# RH036_2.net
KiCad netlist of a schematic drawn in EAGLE
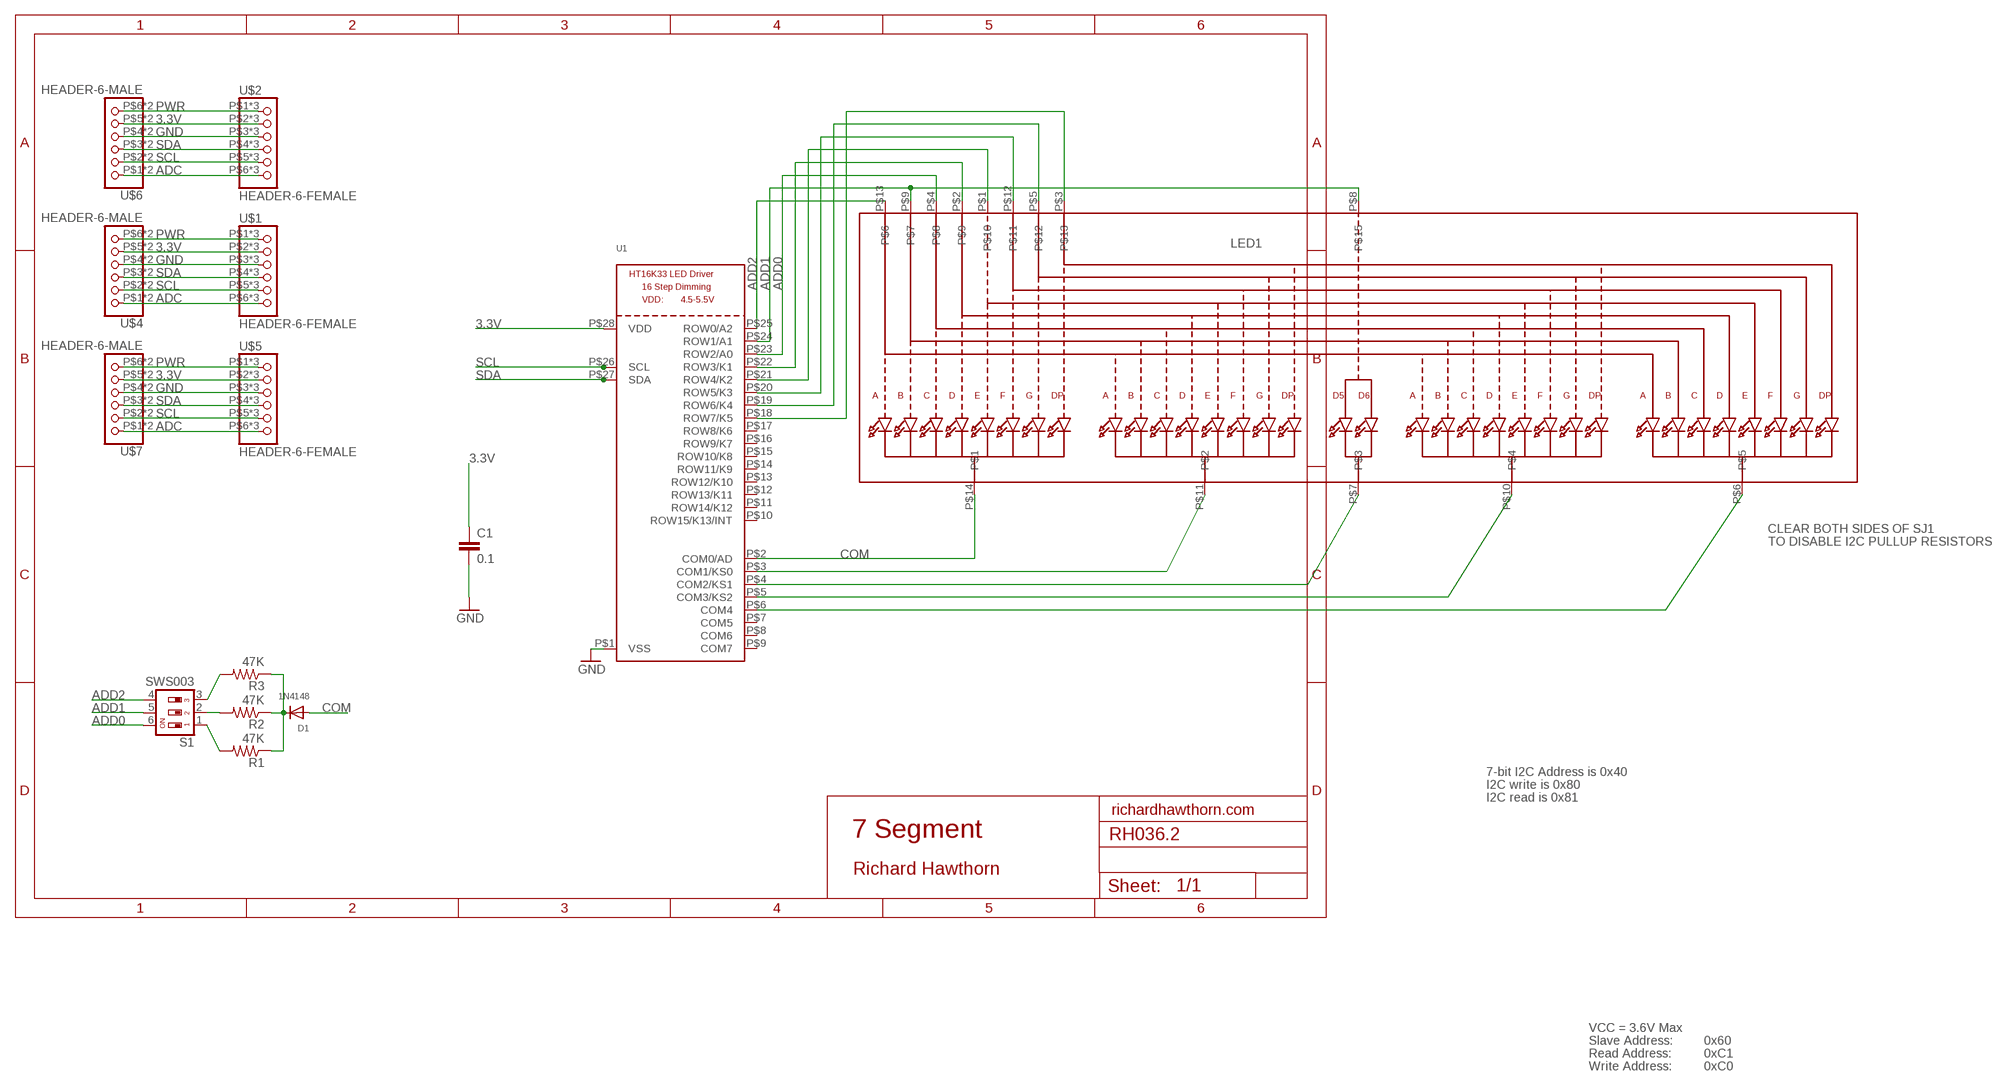
[diagram p0: schematic, sheet 1]

(export (version "E")
  (design (tool "Eeschema 10.0.6"))
  (components
    (comp (ref "C1")
      (value "0.1")
      (footprint "eagle-import:0603-CAP")
      (libsource (lib "eagle-import") (part "CAP0603-CAP"))
    )
    (comp (ref "D1")
      (value "1N4148")
      (footprint "eagle-import:SOD-323F")
      (libsource (lib "eagle-import") (part "DIODESOD-323F"))
    )
    (comp (ref "LED1")
      (value "DISP_SEGMENT_4DIGIT_BL-Q56C43")
      (footprint "eagle-import:SEGMENT-BL-Q56C43")
      (libsource (lib "eagle-import") (part "DISP_SEGMENT_4DIGIT_BL-Q56C43"))
    )
    (comp (ref "R1")
      (value "47K")
      (footprint "eagle-import:R0805")
      (libsource (lib "eagle-import") (part "R-US_R0805"))
    )
    (comp (ref "R2")
      (value "47K")
      (footprint "eagle-import:R0805")
      (libsource (lib "eagle-import") (part "R-US_R0805"))
    )
    (comp (ref "R3")
      (value "47K")
      (footprint "eagle-import:R0805")
      (libsource (lib "eagle-import") (part "R-US_R0805"))
    )
    (comp (ref "S1")
      (value "SWS003")
      (footprint "eagle-import:SMS-003")
      (libsource (lib "eagle-import") (part "SWS003"))
    )
    (comp (ref "U$1")
      (value "HEADER-6-FEMALE")
      (footprint "eagle-import:2MMHEADER6")
      (libsource (lib "eagle-import") (part "HEADER-6-FEMALE"))
    )
    (comp (ref "U$2")
      (value "HEADER-6-FEMALE")
      (footprint "eagle-import:2MMHEADER6")
      (libsource (lib "eagle-import") (part "HEADER-6-FEMALE"))
    )
    (comp (ref "U$4")
      (value "HEADER-6-MALE")
      (footprint "eagle-import:2MMHEADERPIN6")
      (libsource (lib "eagle-import") (part "HEADER-6-MALE"))
    )
    (comp (ref "U$5")
      (value "HEADER-6-FEMALE")
      (footprint "eagle-import:2MMHEADER6")
      (libsource (lib "eagle-import") (part "HEADER-6-FEMALE"))
    )
    (comp (ref "U$6")
      (value "HEADER-6-MALE")
      (footprint "eagle-import:2MMHEADERPIN6")
      (libsource (lib "eagle-import") (part "HEADER-6-MALE"))
    )
    (comp (ref "U$7")
      (value "HEADER-6-MALE")
      (footprint "eagle-import:2MMHEADERPIN6")
      (libsource (lib "eagle-import") (part "HEADER-6-MALE"))
    )
    (comp (ref "U1")
      (value "HT16K33_SOP28")
      (footprint "eagle-import:SOP28_300MIL")
      (libsource (lib "eagle-import") (part "HT16K33_SOP28"))
    )
  )
  (nets
    (net (code "1") (name "/3.3V") (class "Default")
      (node (ref "C1") (pin "1") (pinfunction "1_1") (pintype "passive"))
      (node (ref "U$1") (pin "P$10") (pinfunction "2_P$10") (pintype "passive"))
      (node (ref "U$1") (pin "P$18") (pinfunction "2_P$18") (pintype "passive"))
      (node (ref "U$1") (pin "P$2") (pinfunction "2_P$2") (pintype "passive"))
      (node (ref "U$2") (pin "P$10") (pinfunction "2_P$10") (pintype "passive"))
      (node (ref "U$2") (pin "P$18") (pinfunction "2_P$18") (pintype "passive"))
      (node (ref "U$2") (pin "P$2") (pinfunction "2_P$2") (pintype "passive"))
      (node (ref "U$4") (pin "P$13") (pinfunction "5_P$13") (pintype "passive"))
      (node (ref "U$4") (pin "P$5") (pinfunction "5_P$5") (pintype "passive"))
      (node (ref "U$5") (pin "P$10") (pinfunction "2_P$10") (pintype "passive"))
      (node (ref "U$5") (pin "P$18") (pinfunction "2_P$18") (pintype "passive"))
      (node (ref "U$5") (pin "P$2") (pinfunction "2_P$2") (pintype "passive"))
      (node (ref "U$6") (pin "P$13") (pinfunction "5_P$13") (pintype "passive"))
      (node (ref "U$6") (pin "P$5") (pinfunction "5_P$5") (pintype "passive"))
      (node (ref "U$7") (pin "P$13") (pinfunction "5_P$13") (pintype "passive"))
      (node (ref "U$7") (pin "P$5") (pinfunction "5_P$5") (pintype "passive"))
      (node (ref "U1") (pin "P$28") (pinfunction "VDD_P$28") (pintype "bidirectional"))
    )
    (net (code "2") (name "/ADC") (class "Default")
      (node (ref "U$1") (pin "P$14") (pinfunction "6_P$14") (pintype "passive"))
      (node (ref "U$1") (pin "P$22") (pinfunction "6_P$22") (pintype "passive"))
      (node (ref "U$1") (pin "P$6") (pinfunction "6_P$6") (pintype "passive"))
      (node (ref "U$2") (pin "P$14") (pinfunction "6_P$14") (pintype "passive"))
      (node (ref "U$2") (pin "P$22") (pinfunction "6_P$22") (pintype "passive"))
      (node (ref "U$2") (pin "P$6") (pinfunction "6_P$6") (pintype "passive"))
      (node (ref "U$4") (pin "P$1") (pinfunction "1_P$1") (pintype "passive"))
      (node (ref "U$4") (pin "P$9") (pinfunction "1_P$9") (pintype "passive"))
      (node (ref "U$5") (pin "P$14") (pinfunction "6_P$14") (pintype "passive"))
      (node (ref "U$5") (pin "P$22") (pinfunction "6_P$22") (pintype "passive"))
      (node (ref "U$5") (pin "P$6") (pinfunction "6_P$6") (pintype "passive"))
      (node (ref "U$6") (pin "P$1") (pinfunction "1_P$1") (pintype "passive"))
      (node (ref "U$6") (pin "P$9") (pinfunction "1_P$9") (pintype "passive"))
      (node (ref "U$7") (pin "P$1") (pinfunction "1_P$1") (pintype "passive"))
      (node (ref "U$7") (pin "P$9") (pinfunction "1_P$9") (pintype "passive"))
    )
    (net (code "3") (name "/ADD0") (class "Default")
      (node (ref "LED1") (pin "P$4") (pinfunction "P$8_P$4") (pintype "bidirectional"))
      (node (ref "S1") (pin "6") (pinfunction "6_6") (pintype "passive"))
      (node (ref "U1") (pin "P$23") (pinfunction "ROW2/A0_P$23") (pintype "bidirectional"))
    )
    (net (code "4") (name "/ADD1") (class "Default")
      (node (ref "LED1") (pin "P$8") (pinfunction "P$15_P$8") (pintype "bidirectional"))
      (node (ref "LED1") (pin "P$9") (pinfunction "P$7_P$9") (pintype "bidirectional"))
      (node (ref "S1") (pin "5") (pinfunction "5_5") (pintype "passive"))
      (node (ref "U1") (pin "P$24") (pinfunction "ROW1/A1_P$24") (pintype "bidirectional"))
    )
    (net (code "5") (name "/ADD2") (class "Default")
      (node (ref "LED1") (pin "P$13") (pinfunction "P$6_P$13") (pintype "bidirectional"))
      (node (ref "S1") (pin "4") (pinfunction "4_4") (pintype "passive"))
      (node (ref "U1") (pin "P$25") (pinfunction "ROW0/A2_P$25") (pintype "bidirectional"))
    )
    (net (code "6") (name "/COM") (class "Default")
      (node (ref "D1") (pin "A") (pinfunction "A_A") (pintype "passive"))
      (node (ref "LED1") (pin "P$14") (pinfunction "P$1_P$14") (pintype "bidirectional"))
      (node (ref "U1") (pin "P$2") (pinfunction "COM0/AD_P$2") (pintype "bidirectional"))
    )
    (net (code "7") (name "/PWR") (class "Default")
      (node (ref "U$1") (pin "P$1") (pinfunction "1_P$1") (pintype "passive"))
      (node (ref "U$1") (pin "P$17") (pinfunction "1_P$17") (pintype "passive"))
      (node (ref "U$1") (pin "P$9") (pinfunction "1_P$9") (pintype "passive"))
      (node (ref "U$2") (pin "P$1") (pinfunction "1_P$1") (pintype "passive"))
      (node (ref "U$2") (pin "P$17") (pinfunction "1_P$17") (pintype "passive"))
      (node (ref "U$2") (pin "P$9") (pinfunction "1_P$9") (pintype "passive"))
      (node (ref "U$4") (pin "P$14") (pinfunction "6_P$14") (pintype "passive"))
      (node (ref "U$4") (pin "P$6") (pinfunction "6_P$6") (pintype "passive"))
      (node (ref "U$5") (pin "P$1") (pinfunction "1_P$1") (pintype "passive"))
      (node (ref "U$5") (pin "P$17") (pinfunction "1_P$17") (pintype "passive"))
      (node (ref "U$5") (pin "P$9") (pinfunction "1_P$9") (pintype "passive"))
      (node (ref "U$6") (pin "P$14") (pinfunction "6_P$14") (pintype "passive"))
      (node (ref "U$6") (pin "P$6") (pinfunction "6_P$6") (pintype "passive"))
      (node (ref "U$7") (pin "P$14") (pinfunction "6_P$14") (pintype "passive"))
      (node (ref "U$7") (pin "P$6") (pinfunction "6_P$6") (pintype "passive"))
    )
    (net (code "8") (name "/SCL") (class "Default")
      (node (ref "U$1") (pin "P$13") (pinfunction "5_P$13") (pintype "passive"))
      (node (ref "U$1") (pin "P$21") (pinfunction "5_P$21") (pintype "passive"))
      (node (ref "U$1") (pin "P$5") (pinfunction "5_P$5") (pintype "passive"))
      (node (ref "U$2") (pin "P$13") (pinfunction "5_P$13") (pintype "passive"))
      (node (ref "U$2") (pin "P$21") (pinfunction "5_P$21") (pintype "passive"))
      (node (ref "U$2") (pin "P$5") (pinfunction "5_P$5") (pintype "passive"))
      (node (ref "U$4") (pin "P$10") (pinfunction "2_P$10") (pintype "passive"))
      (node (ref "U$4") (pin "P$2") (pinfunction "2_P$2") (pintype "passive"))
      (node (ref "U$5") (pin "P$13") (pinfunction "5_P$13") (pintype "passive"))
      (node (ref "U$5") (pin "P$21") (pinfunction "5_P$21") (pintype "passive"))
      (node (ref "U$5") (pin "P$5") (pinfunction "5_P$5") (pintype "passive"))
      (node (ref "U$6") (pin "P$10") (pinfunction "2_P$10") (pintype "passive"))
      (node (ref "U$6") (pin "P$2") (pinfunction "2_P$2") (pintype "passive"))
      (node (ref "U$7") (pin "P$10") (pinfunction "2_P$10") (pintype "passive"))
      (node (ref "U$7") (pin "P$2") (pinfunction "2_P$2") (pintype "passive"))
      (node (ref "U1") (pin "P$26") (pinfunction "SCL_P$26") (pintype "bidirectional"))
    )
    (net (code "9") (name "/SDA") (class "Default")
      (node (ref "U$1") (pin "P$12") (pinfunction "4_P$12") (pintype "passive"))
      (node (ref "U$1") (pin "P$20") (pinfunction "4_P$20") (pintype "passive"))
      (node (ref "U$1") (pin "P$4") (pinfunction "4_P$4") (pintype "passive"))
      (node (ref "U$2") (pin "P$12") (pinfunction "4_P$12") (pintype "passive"))
      (node (ref "U$2") (pin "P$20") (pinfunction "4_P$20") (pintype "passive"))
      (node (ref "U$2") (pin "P$4") (pinfunction "4_P$4") (pintype "passive"))
      (node (ref "U$4") (pin "P$11") (pinfunction "3_P$11") (pintype "passive"))
      (node (ref "U$4") (pin "P$3") (pinfunction "3_P$3") (pintype "passive"))
      (node (ref "U$5") (pin "P$12") (pinfunction "4_P$12") (pintype "passive"))
      (node (ref "U$5") (pin "P$20") (pinfunction "4_P$20") (pintype "passive"))
      (node (ref "U$5") (pin "P$4") (pinfunction "4_P$4") (pintype "passive"))
      (node (ref "U$6") (pin "P$11") (pinfunction "3_P$11") (pintype "passive"))
      (node (ref "U$6") (pin "P$3") (pinfunction "3_P$3") (pintype "passive"))
      (node (ref "U$7") (pin "P$11") (pinfunction "3_P$11") (pintype "passive"))
      (node (ref "U$7") (pin "P$3") (pinfunction "3_P$3") (pintype "passive"))
      (node (ref "U1") (pin "P$27") (pinfunction "SDA_P$27") (pintype "bidirectional"))
    )
    (net (code "10") (name "GND") (class "Default")
      (node (ref "C1") (pin "2") (pinfunction "2_2") (pintype "passive"))
      (node (ref "U$1") (pin "P$11") (pinfunction "3_P$11") (pintype "passive"))
      (node (ref "U$1") (pin "P$19") (pinfunction "3_P$19") (pintype "passive"))
      (node (ref "U$1") (pin "P$3") (pinfunction "3_P$3") (pintype "passive"))
      (node (ref "U$2") (pin "P$11") (pinfunction "3_P$11") (pintype "passive"))
      (node (ref "U$2") (pin "P$19") (pinfunction "3_P$19") (pintype "passive"))
      (node (ref "U$2") (pin "P$3") (pinfunction "3_P$3") (pintype "passive"))
      (node (ref "U$4") (pin "P$12") (pinfunction "4_P$12") (pintype "passive"))
      (node (ref "U$4") (pin "P$4") (pinfunction "4_P$4") (pintype "passive"))
      (node (ref "U$5") (pin "P$11") (pinfunction "3_P$11") (pintype "passive"))
      (node (ref "U$5") (pin "P$19") (pinfunction "3_P$19") (pintype "passive"))
      (node (ref "U$5") (pin "P$3") (pinfunction "3_P$3") (pintype "passive"))
      (node (ref "U$6") (pin "P$12") (pinfunction "4_P$12") (pintype "passive"))
      (node (ref "U$6") (pin "P$4") (pinfunction "4_P$4") (pintype "passive"))
      (node (ref "U$7") (pin "P$12") (pinfunction "4_P$12") (pintype "passive"))
      (node (ref "U$7") (pin "P$4") (pinfunction "4_P$4") (pintype "passive"))
      (node (ref "U1") (pin "P$1") (pinfunction "VSS_P$1") (pintype "bidirectional"))
    )
    (net (code "11") (name "Net-(D1-PadC)") (class "Default")
      (node (ref "D1") (pin "C") (pinfunction "C_C") (pintype "passive"))
      (node (ref "R1") (pin "1") (pinfunction "1_1") (pintype "passive"))
      (node (ref "R2") (pin "1") (pinfunction "1_1") (pintype "passive"))
      (node (ref "R3") (pin "1") (pinfunction "1_1") (pintype "passive"))
    )
    (net (code "12") (name "Net-(LED1-P$2)") (class "Default")
      (node (ref "LED1") (pin "P$11") (pinfunction "P$2_P$11") (pintype "bidirectional"))
      (node (ref "U1") (pin "P$3") (pinfunction "COM1/KS0_P$3") (pintype "bidirectional"))
    )
    (net (code "13") (name "Net-(LED1-P$3)") (class "Default")
      (node (ref "LED1") (pin "P$7") (pinfunction "P$3_P$7") (pintype "bidirectional"))
      (node (ref "U1") (pin "P$4") (pinfunction "COM2/KS1_P$4") (pintype "bidirectional"))
    )
    (net (code "14") (name "Net-(LED1-P$4)") (class "Default")
      (node (ref "LED1") (pin "P$10") (pinfunction "P$4_P$10") (pintype "bidirectional"))
      (node (ref "U1") (pin "P$5") (pinfunction "COM3/KS2_P$5") (pintype "bidirectional"))
    )
    (net (code "15") (name "Net-(LED1-P$5)") (class "Default")
      (node (ref "LED1") (pin "P$6") (pinfunction "P$5_P$6") (pintype "bidirectional"))
      (node (ref "U1") (pin "P$6") (pinfunction "COM4_P$6") (pintype "bidirectional"))
    )
    (net (code "16") (name "Net-(LED1-P$9)") (class "Default")
      (node (ref "LED1") (pin "P$2") (pinfunction "P$9_P$2") (pintype "bidirectional"))
      (node (ref "U1") (pin "P$22") (pinfunction "ROW3/K1_P$22") (pintype "bidirectional"))
    )
    (net (code "17") (name "Net-(LED1-P$10)") (class "Default")
      (node (ref "LED1") (pin "P$1") (pinfunction "P$10_P$1") (pintype "bidirectional"))
      (node (ref "U1") (pin "P$21") (pinfunction "ROW4/K2_P$21") (pintype "bidirectional"))
    )
    (net (code "18") (name "Net-(LED1-P$11)") (class "Default")
      (node (ref "LED1") (pin "P$12") (pinfunction "P$11_P$12") (pintype "bidirectional"))
      (node (ref "U1") (pin "P$20") (pinfunction "ROW5/K3_P$20") (pintype "bidirectional"))
    )
    (net (code "19") (name "Net-(LED1-P$12)") (class "Default")
      (node (ref "LED1") (pin "P$5") (pinfunction "P$12_P$5") (pintype "bidirectional"))
      (node (ref "U1") (pin "P$19") (pinfunction "ROW6/K4_P$19") (pintype "bidirectional"))
    )
    (net (code "20") (name "Net-(LED1-P$13)") (class "Default")
      (node (ref "LED1") (pin "P$3") (pinfunction "P$13_P$3") (pintype "bidirectional"))
      (node (ref "U1") (pin "P$18") (pinfunction "ROW7/K5_P$18") (pintype "bidirectional"))
    )
    (net (code "21") (name "Net-(R1-Pad2)") (class "Default")
      (node (ref "R1") (pin "2") (pinfunction "2_2") (pintype "passive"))
      (node (ref "S1") (pin "1") (pinfunction "1_1") (pintype "passive"))
    )
    (net (code "22") (name "Net-(R2-Pad2)") (class "Default")
      (node (ref "R2") (pin "2") (pinfunction "2_2") (pintype "passive"))
      (node (ref "S1") (pin "2") (pinfunction "2_2") (pintype "passive"))
    )
    (net (code "23") (name "Net-(R3-Pad2)") (class "Default")
      (node (ref "R3") (pin "2") (pinfunction "2_2") (pintype "passive"))
      (node (ref "S1") (pin "3") (pinfunction "3_3") (pintype "passive"))
    )
    (net (code "24") (name "unconnected-(U1-COM5-PadP$7)") (class "Default")
      (node (ref "U1") (pin "P$7") (pinfunction "COM5_P$7") (pintype "bidirectional"))
    )
    (net (code "25") (name "unconnected-(U1-COM6-PadP$8)") (class "Default")
      (node (ref "U1") (pin "P$8") (pinfunction "COM6_P$8") (pintype "bidirectional"))
    )
    (net (code "26") (name "unconnected-(U1-COM7-PadP$9)") (class "Default")
      (node (ref "U1") (pin "P$9") (pinfunction "COM7_P$9") (pintype "bidirectional"))
    )
    (net (code "27") (name "unconnected-(U1-ROW8{slash}K6-PadP$17)") (class "Default")
      (node (ref "U1") (pin "P$17") (pinfunction "ROW8/K6_P$17") (pintype "bidirectional"))
    )
    (net (code "28") (name "unconnected-(U1-ROW9{slash}K7-PadP$16)") (class "Default")
      (node (ref "U1") (pin "P$16") (pinfunction "ROW9/K7_P$16") (pintype "bidirectional"))
    )
    (net (code "29") (name "unconnected-(U1-ROW10{slash}K8-PadP$15)") (class "Default")
      (node (ref "U1") (pin "P$15") (pinfunction "ROW10/K8_P$15") (pintype "bidirectional"))
    )
    (net (code "30") (name "unconnected-(U1-ROW11{slash}K9-PadP$14)") (class "Default")
      (node (ref "U1") (pin "P$14") (pinfunction "ROW11/K9_P$14") (pintype "bidirectional"))
    )
    (net (code "31") (name "unconnected-(U1-ROW12{slash}K10-PadP$13)") (class "Default")
      (node (ref "U1") (pin "P$13") (pinfunction "ROW12/K10_P$13") (pintype "bidirectional"))
    )
    (net (code "32") (name "unconnected-(U1-ROW13{slash}K11-PadP$12)") (class "Default")
      (node (ref "U1") (pin "P$12") (pinfunction "ROW13/K11_P$12") (pintype "bidirectional"))
    )
    (net (code "33") (name "unconnected-(U1-ROW14{slash}K12-PadP$11)") (class "Default")
      (node (ref "U1") (pin "P$11") (pinfunction "ROW14/K12_P$11") (pintype "bidirectional"))
    )
    (net (code "34") (name "unconnected-(U1-ROW15{slash}K13{slash}INT-PadP$10)") (class "Default")
      (node (ref "U1") (pin "P$10") (pinfunction "ROW15/K13/INT_P$10") (pintype "bidirectional"))
    )
  )
)
